# JTAG_Connector.net
KiCad netlist of a schematic drawn in Altium Designer
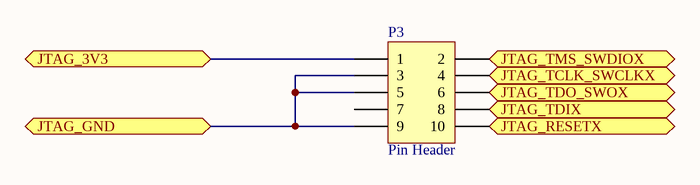
[diagram p0: JTAG Connector.SchDoc]

(export (version "E")
  (design (tool "Eeschema 10.0.6"))
  (components
    (comp (ref "P3")
      (value "Pin Header")
      (footprint "PH2x5_2.54")
      (description "Header, 5-Pin, Dual row")
      (fields (field (name "PART NUMBER") "PH2x5") (field (name "AUTHOR") "Willy Pietersz"))
      (libsource (lib "OurDb") (part "Con2x5"))
    )
  )
  (nets
    (net (code "1") (name "/JTAG_3V3") (class "Default")
      (node (ref "P3") (pin "1") (pinfunction "1_1") (pintype "passive"))
    )
    (net (code "2") (name "/JTAG_GND") (class "Default")
      (node (ref "P3") (pin "3") (pinfunction "3_3") (pintype "passive"))
      (node (ref "P3") (pin "5") (pinfunction "5_5") (pintype "passive"))
      (node (ref "P3") (pin "9") (pinfunction "9_9") (pintype "passive"))
    )
    (net (code "3") (name "/JTAG_RESETX") (class "Default")
      (node (ref "P3") (pin "10") (pinfunction "10_10") (pintype "passive"))
    )
    (net (code "4") (name "/JTAG_TCLK_SWCLKX") (class "Default")
      (node (ref "P3") (pin "4") (pinfunction "4_4") (pintype "passive"))
    )
    (net (code "5") (name "/JTAG_TDIX") (class "Default")
      (node (ref "P3") (pin "8") (pinfunction "8_8") (pintype "passive"))
    )
    (net (code "6") (name "/JTAG_TDO_SWOX") (class "Default")
      (node (ref "P3") (pin "6") (pinfunction "6_6") (pintype "passive"))
    )
    (net (code "7") (name "/JTAG_TMS_SWDIOX") (class "Default")
      (node (ref "P3") (pin "2") (pinfunction "2_2") (pintype "passive"))
    )
    (net (code "8") (name "unconnected-(P3-Pad7)") (class "Default")
      (node (ref "P3") (pin "7") (pinfunction "7_7") (pintype "passive"))
    )
  )
)
